# MSP432.net
KiCad netlist of a schematic drawn in Altium Designer
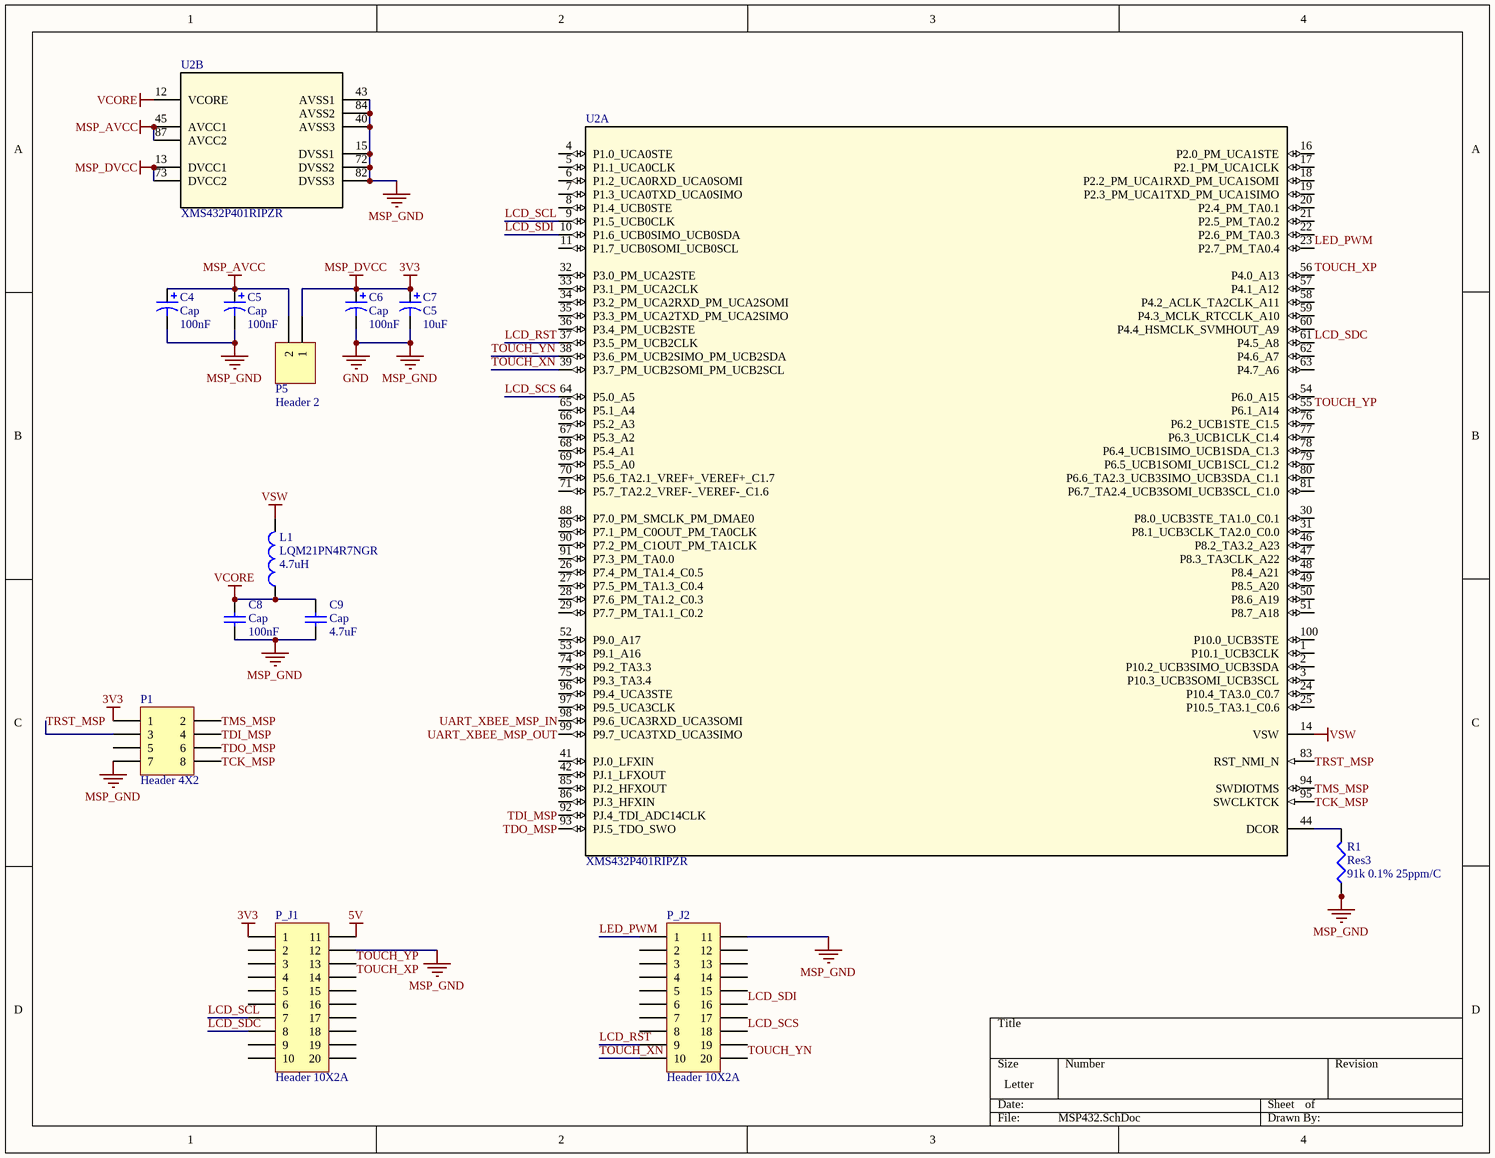
[diagram p0: MSP432.SchDoc]

(export (version "E")
  (design (tool "Eeschema 10.0.6"))
  (components
    (comp (ref "C4")
      (value "Cap")
      (footprint "C0805")
      (description "Polarized Capacitor (Surface Mount)")
      (fields (field (name "ALTIUM_VALUE") "100nF") (field (name "PUBLISHER") "Altium Limited"))
      (libsource (lib "Miscellaneous Devices") (part "Cap Pol3"))
    )
    (comp (ref "C5")
      (value "Cap")
      (footprint "C0805")
      (description "Polarized Capacitor (Surface Mount)")
      (fields (field (name "ALTIUM_VALUE") "100nF") (field (name "PUBLISHER") "Altium Limited"))
      (libsource (lib "Miscellaneous Devices") (part "Cap Pol3"))
    )
    (comp (ref "C6")
      (value "Cap")
      (footprint "C0805")
      (description "Polarized Capacitor (Surface Mount)")
      (fields (field (name "ALTIUM_VALUE") "100nF") (field (name "PUBLISHER") "Altium Limited"))
      (libsource (lib "Miscellaneous Devices") (part "Cap Pol3"))
    )
    (comp (ref "C7")
      (value "C5")
      (footprint "C0805")
      (description "Polarized Capacitor (Surface Mount)")
      (fields (field (name "ALTIUM_VALUE") "10uF") (field (name "PUBLISHER") "Altium Limited"))
      (libsource (lib "Miscellaneous Devices") (part "Cap Pol3"))
    )
    (comp (ref "C8")
      (value "Cap")
      (footprint "C0805")
      (description "Capacitor (Semiconductor SIM Model)")
      (fields (field (name "ALTIUM_VALUE") "100nF") (field (name "PUBLISHER") "Altium Limited"))
      (libsource (lib "Miscellaneous Devices") (part "Cap Semi"))
    )
    (comp (ref "C9")
      (value "Cap")
      (footprint "C0805")
      (description "Capacitor (Semiconductor SIM Model)")
      (fields (field (name "ALTIUM_VALUE") "4.7uF") (field (name "PUBLISHER") "Altium Limited"))
      (libsource (lib "Miscellaneous Devices") (part "Cap Semi"))
    )
    (comp (ref "L1")
      (value "LQM21PN4R7NGR")
      (footprint "6-0805_N")
      (description "Inductor")
      (fields (field (name "ALTIUM_VALUE") "4.7uH") (field (name "PUBLISHER") "Altium Limited"))
      (libsource (lib "Miscellaneous Devices") (part "Inductor"))
    )
    (comp (ref "P1")
      (value "Header 4X2")
      (footprint "HDR2X4")
      (description "Header, 4-Pin, Dual row")
      (fields (field (name "PUBLISHER") "Altium Limited"))
      (libsource (lib "Miscellaneous Connectors") (part "Header 4X2"))
    )
    (comp (ref "P5")
      (value "Header 2")
      (footprint "HDR1X2")
      (description "Header, 2-Pin")
      (fields (field (name "PUBLISHER") "Altium Limited"))
      (libsource (lib "Miscellaneous Connectors") (part "Header 2"))
    )
    (comp (ref "P_J1")
      (value "Header 10X2A")
      (footprint "HDR2X10_CEN")
      (description "Header, 10-Pin, Dual row")
      (fields (field (name "PUBLISHER") "Altium Limited"))
      (libsource (lib "Miscellaneous Connectors") (part "Header 10X2A"))
    )
    (comp (ref "P_J2")
      (value "Header 10X2A")
      (footprint "HDR2X10_CEN")
      (description "Header, 10-Pin, Dual row")
      (fields (field (name "PUBLISHER") "Altium Limited"))
      (libsource (lib "Miscellaneous Connectors") (part "Header 10X2A"))
    )
    (comp (ref "R1")
      (value "Res3")
      (footprint "14-1210")
      (description "Resistor")
      (fields (field (name "ALTIUM_VALUE") "91k 0.1% 25ppm/C") (field (name "PUBLISHER") "Altium Limited"))
      (libsource (lib "Miscellaneous Devices") (part "Res3"))
    )
    (comp (ref "U2")
      (value "XMS432P401RIPZR")
      (footprint "PZ0100A_N")
      (description "Imported")
      (fields (field (name "MANUFACTURER") "Texas Instruments"))
      (libsource (lib "XMS432P401R") (part "XMS432P401RIPZR"))
    )
  )
  (nets
    (net (code "1") (name "/LCD_RST") (class "Default")
      (node (ref "P_J2") (pin "9") (pinfunction "9_9") (pintype "passive"))
      (node (ref "U2") (pin "37") (pinfunction "P3.5_PM_UCB2CLK_37") (pintype "bidirectional"))
    )
    (net (code "2") (name "/LCD_SCL") (class "Default")
      (node (ref "P_J1") (pin "7") (pinfunction "7_7") (pintype "passive"))
      (node (ref "U2") (pin "9") (pinfunction "P1.5_UCB0CLK_9") (pintype "bidirectional"))
    )
    (net (code "3") (name "/LCD_SCS") (class "Default")
      (node (ref "P_J2") (pin "18") (pinfunction "18_18") (pintype "passive"))
      (node (ref "U2") (pin "64") (pinfunction "P5.0_A5_64") (pintype "bidirectional"))
    )
    (net (code "4") (name "/LCD_SDC") (class "Default")
      (node (ref "P_J1") (pin "8") (pinfunction "8_8") (pintype "passive"))
      (node (ref "U2") (pin "61") (pinfunction "P4.5_A8_61") (pintype "bidirectional"))
    )
    (net (code "5") (name "/LCD_SDI") (class "Default")
      (node (ref "P_J2") (pin "16") (pinfunction "16_16") (pintype "passive"))
      (node (ref "U2") (pin "10") (pinfunction "P1.6_UCB0SIMO_UCB0SDA_10") (pintype "bidirectional"))
    )
    (net (code "6") (name "/LED_PWM") (class "Default")
      (node (ref "P_J2") (pin "1") (pinfunction "1_1") (pintype "passive"))
      (node (ref "U2") (pin "23") (pinfunction "P2.7_PM_TA0.4_23") (pintype "bidirectional"))
    )
    (net (code "7") (name "/TCK_MSP") (class "Default")
      (node (ref "P1") (pin "8") (pinfunction "8_8") (pintype "passive"))
      (node (ref "U2") (pin "95") (pinfunction "SWCLKTCK_95") (pintype "input"))
    )
    (net (code "8") (name "/TDI_MSP") (class "Default")
      (node (ref "P1") (pin "4") (pinfunction "4_4") (pintype "passive"))
      (node (ref "U2") (pin "92") (pinfunction "PJ.4_TDI_ADC14CLK_92") (pintype "bidirectional"))
    )
    (net (code "9") (name "/TDO_MSP") (class "Default")
      (node (ref "P1") (pin "6") (pinfunction "6_6") (pintype "passive"))
      (node (ref "U2") (pin "93") (pinfunction "PJ.5_TDO_SWO_93") (pintype "bidirectional"))
    )
    (net (code "10") (name "/TMS_MSP") (class "Default")
      (node (ref "P1") (pin "2") (pinfunction "2_2") (pintype "passive"))
      (node (ref "U2") (pin "94") (pinfunction "SWDIOTMS_94") (pintype "bidirectional"))
    )
    (net (code "11") (name "/TOUCH_XN") (class "Default")
      (node (ref "P_J2") (pin "10") (pinfunction "10_10") (pintype "passive"))
      (node (ref "U2") (pin "39") (pinfunction "P3.7_PM_UCB2SOMI_PM_UCB2SCL_39") (pintype "bidirectional"))
    )
    (net (code "12") (name "/TOUCH_XP") (class "Default")
      (node (ref "P_J1") (pin "14") (pinfunction "14_14") (pintype "passive"))
      (node (ref "U2") (pin "56") (pinfunction "P4.0_A13_56") (pintype "bidirectional"))
    )
    (net (code "13") (name "/TOUCH_YN") (class "Default")
      (node (ref "P_J2") (pin "20") (pinfunction "20_20") (pintype "passive"))
      (node (ref "U2") (pin "38") (pinfunction "P3.6_PM_UCB2SIMO_PM_UCB2SDA_38") (pintype "bidirectional"))
    )
    (net (code "14") (name "/TOUCH_YP") (class "Default")
      (node (ref "P_J1") (pin "13") (pinfunction "13_13") (pintype "passive"))
      (node (ref "U2") (pin "55") (pinfunction "P6.1_A14_55") (pintype "bidirectional"))
    )
    (net (code "15") (name "/TRST_MSP") (class "Default")
      (node (ref "P1") (pin "3") (pinfunction "3_3") (pintype "passive"))
      (node (ref "U2") (pin "83") (pinfunction "RST_NMI_N_83") (pintype "input"))
    )
    (net (code "16") (name "/UART_XBEE_MSP_IN") (class "Default")
      (node (ref "U2") (pin "98") (pinfunction "P9.6_UCA3RXD_UCA3SOMI_98") (pintype "bidirectional"))
    )
    (net (code "17") (name "/UART_XBEE_MSP_OUT") (class "Default")
      (node (ref "U2") (pin "99") (pinfunction "P9.7_UCA3TXD_UCA3SIMO_99") (pintype "bidirectional"))
    )
    (net (code "18") (name "3V3") (class "Default")
      (node (ref "C6") (pin "1") (pinfunction "1_1") (pintype "passive"))
      (node (ref "C7") (pin "1") (pinfunction "1_1") (pintype "passive"))
      (node (ref "P1") (pin "1") (pinfunction "1_1") (pintype "passive"))
      (node (ref "P5") (pin "1") (pinfunction "1_1") (pintype "passive"))
      (node (ref "P_J1") (pin "1") (pinfunction "1_1") (pintype "passive"))
      (node (ref "U2") (pin "13") (pinfunction "DVCC1_13") (pintype "power_in"))
      (node (ref "U2") (pin "73") (pinfunction "DVCC2_73") (pintype "power_in"))
    )
    (net (code "19") (name "5V") (class "Default")
      (node (ref "P_J1") (pin "11") (pinfunction "11_11") (pintype "passive"))
    )
    (net (code "20") (name "GND") (class "Default")
      (node (ref "C4") (pin "2") (pinfunction "2_2") (pintype "passive"))
      (node (ref "C5") (pin "2") (pinfunction "2_2") (pintype "passive"))
      (node (ref "C6") (pin "2") (pinfunction "2_2") (pintype "passive"))
      (node (ref "C7") (pin "2") (pinfunction "2_2") (pintype "passive"))
      (node (ref "C8") (pin "1") (pinfunction "1_1") (pintype "passive"))
      (node (ref "C9") (pin "2") (pinfunction "2_2") (pintype "passive"))
      (node (ref "P1") (pin "7") (pinfunction "7_7") (pintype "passive"))
      (node (ref "P_J1") (pin "12") (pinfunction "12_12") (pintype "passive"))
      (node (ref "P_J2") (pin "11") (pinfunction "11_11") (pintype "passive"))
      (node (ref "R1") (pin "1") (pinfunction "1_1") (pintype "passive"))
      (node (ref "U2") (pin "15") (pinfunction "DVSS1_15") (pintype "power_in"))
      (node (ref "U2") (pin "40") (pinfunction "AVSS3_40") (pintype "power_in"))
      (node (ref "U2") (pin "43") (pinfunction "AVSS1_43") (pintype "power_in"))
      (node (ref "U2") (pin "72") (pinfunction "DVSS2_72") (pintype "power_in"))
      (node (ref "U2") (pin "82") (pinfunction "DVSS3_82") (pintype "power_in"))
      (node (ref "U2") (pin "84") (pinfunction "AVSS2_84") (pintype "power_in"))
    )
    (net (code "21") (name "MSP_AVCC") (class "Default")
      (node (ref "C4") (pin "1") (pinfunction "1_1") (pintype "passive"))
      (node (ref "C5") (pin "1") (pinfunction "1_1") (pintype "passive"))
      (node (ref "P5") (pin "2") (pinfunction "2_2") (pintype "passive"))
      (node (ref "U2") (pin "45") (pinfunction "AVCC1_45") (pintype "power_in"))
      (node (ref "U2") (pin "87") (pinfunction "AVCC2_87") (pintype "power_in"))
    )
    (net (code "22") (name "Net-(U2A-DCOR)") (class "Default")
      (node (ref "R1") (pin "2") (pinfunction "2_2") (pintype "passive"))
      (node (ref "U2") (pin "44") (pinfunction "DCOR_44") (pintype "passive"))
    )
    (net (code "23") (name "VCORE") (class "Default")
      (node (ref "C8") (pin "2") (pinfunction "2_2") (pintype "passive"))
      (node (ref "C9") (pin "1") (pinfunction "1_1") (pintype "passive"))
      (node (ref "L1") (pin "1") (pinfunction "1_1") (pintype "passive"))
      (node (ref "U2") (pin "12") (pinfunction "VCORE_12") (pintype "power_in"))
    )
    (net (code "24") (name "VSW") (class "Default")
      (node (ref "L1") (pin "2") (pinfunction "2_2") (pintype "passive"))
      (node (ref "U2") (pin "14") (pinfunction "VSW_14") (pintype "passive"))
    )
    (net (code "25") (name "unconnected-(P1-Pad5)") (class "Default")
      (node (ref "P1") (pin "5") (pinfunction "5_5") (pintype "passive"))
    )
    (net (code "26") (name "unconnected-(P_J1-Pad2)") (class "Default")
      (node (ref "P_J1") (pin "2") (pinfunction "2_2") (pintype "passive"))
    )
    (net (code "27") (name "unconnected-(P_J1-Pad3)") (class "Default")
      (node (ref "P_J1") (pin "3") (pinfunction "3_3") (pintype "passive"))
    )
    (net (code "28") (name "unconnected-(P_J1-Pad4)") (class "Default")
      (node (ref "P_J1") (pin "4") (pinfunction "4_4") (pintype "passive"))
    )
    (net (code "29") (name "unconnected-(P_J1-Pad5)") (class "Default")
      (node (ref "P_J1") (pin "5") (pinfunction "5_5") (pintype "passive"))
    )
    (net (code "30") (name "unconnected-(P_J1-Pad6)") (class "Default")
      (node (ref "P_J1") (pin "6") (pinfunction "6_6") (pintype "passive"))
    )
    (net (code "31") (name "unconnected-(P_J1-Pad9)") (class "Default")
      (node (ref "P_J1") (pin "9") (pinfunction "9_9") (pintype "passive"))
    )
    (net (code "32") (name "unconnected-(P_J1-Pad10)") (class "Default")
      (node (ref "P_J1") (pin "10") (pinfunction "10_10") (pintype "passive"))
    )
    (net (code "33") (name "unconnected-(P_J1-Pad15)") (class "Default")
      (node (ref "P_J1") (pin "15") (pinfunction "15_15") (pintype "passive"))
    )
    (net (code "34") (name "unconnected-(P_J1-Pad16)") (class "Default")
      (node (ref "P_J1") (pin "16") (pinfunction "16_16") (pintype "passive"))
    )
    (net (code "35") (name "unconnected-(P_J1-Pad17)") (class "Default")
      (node (ref "P_J1") (pin "17") (pinfunction "17_17") (pintype "passive"))
    )
    (net (code "36") (name "unconnected-(P_J1-Pad18)") (class "Default")
      (node (ref "P_J1") (pin "18") (pinfunction "18_18") (pintype "passive"))
    )
    (net (code "37") (name "unconnected-(P_J1-Pad19)") (class "Default")
      (node (ref "P_J1") (pin "19") (pinfunction "19_19") (pintype "passive"))
    )
    (net (code "38") (name "unconnected-(P_J1-Pad20)") (class "Default")
      (node (ref "P_J1") (pin "20") (pinfunction "20_20") (pintype "passive"))
    )
    (net (code "39") (name "unconnected-(P_J2-Pad2)") (class "Default")
      (node (ref "P_J2") (pin "2") (pinfunction "2_2") (pintype "passive"))
    )
    (net (code "40") (name "unconnected-(P_J2-Pad3)") (class "Default")
      (node (ref "P_J2") (pin "3") (pinfunction "3_3") (pintype "passive"))
    )
    (net (code "41") (name "unconnected-(P_J2-Pad4)") (class "Default")
      (node (ref "P_J2") (pin "4") (pinfunction "4_4") (pintype "passive"))
    )
    (net (code "42") (name "unconnected-(P_J2-Pad5)") (class "Default")
      (node (ref "P_J2") (pin "5") (pinfunction "5_5") (pintype "passive"))
    )
    (net (code "43") (name "unconnected-(P_J2-Pad6)") (class "Default")
      (node (ref "P_J2") (pin "6") (pinfunction "6_6") (pintype "passive"))
    )
    (net (code "44") (name "unconnected-(P_J2-Pad7)") (class "Default")
      (node (ref "P_J2") (pin "7") (pinfunction "7_7") (pintype "passive"))
    )
    (net (code "45") (name "unconnected-(P_J2-Pad8)") (class "Default")
      (node (ref "P_J2") (pin "8") (pinfunction "8_8") (pintype "passive"))
    )
    (net (code "46") (name "unconnected-(P_J2-Pad12)") (class "Default")
      (node (ref "P_J2") (pin "12") (pinfunction "12_12") (pintype "passive"))
    )
    (net (code "47") (name "unconnected-(P_J2-Pad13)") (class "Default")
      (node (ref "P_J2") (pin "13") (pinfunction "13_13") (pintype "passive"))
    )
    (net (code "48") (name "unconnected-(P_J2-Pad14)") (class "Default")
      (node (ref "P_J2") (pin "14") (pinfunction "14_14") (pintype "passive"))
    )
    (net (code "49") (name "unconnected-(P_J2-Pad15)") (class "Default")
      (node (ref "P_J2") (pin "15") (pinfunction "15_15") (pintype "passive"))
    )
    (net (code "50") (name "unconnected-(P_J2-Pad17)") (class "Default")
      (node (ref "P_J2") (pin "17") (pinfunction "17_17") (pintype "passive"))
    )
    (net (code "51") (name "unconnected-(P_J2-Pad19)") (class "Default")
      (node (ref "P_J2") (pin "19") (pinfunction "19_19") (pintype "passive"))
    )
    (net (code "52") (name "unconnected-(U2A-P1.0_UCA0STE-Pad4)") (class "Default")
      (node (ref "U2") (pin "4") (pinfunction "P1.0_UCA0STE_4") (pintype "bidirectional"))
    )
    (net (code "53") (name "unconnected-(U2A-P1.1_UCA0CLK-Pad5)") (class "Default")
      (node (ref "U2") (pin "5") (pinfunction "P1.1_UCA0CLK_5") (pintype "bidirectional"))
    )
    (net (code "54") (name "unconnected-(U2A-P1.2_UCA0RXD_UCA0SOMI-Pad6)") (class "Default")
      (node (ref "U2") (pin "6") (pinfunction "P1.2_UCA0RXD_UCA0SOMI_6") (pintype "bidirectional"))
    )
    (net (code "55") (name "unconnected-(U2A-P1.3_UCA0TXD_UCA0SIMO-Pad7)") (class "Default")
      (node (ref "U2") (pin "7") (pinfunction "P1.3_UCA0TXD_UCA0SIMO_7") (pintype "bidirectional"))
    )
    (net (code "56") (name "unconnected-(U2A-P1.4_UCB0STE-Pad8)") (class "Default")
      (node (ref "U2") (pin "8") (pinfunction "P1.4_UCB0STE_8") (pintype "bidirectional"))
    )
    (net (code "57") (name "unconnected-(U2A-P1.7_UCB0SOMI_UCB0SCL-Pad11)") (class "Default")
      (node (ref "U2") (pin "11") (pinfunction "P1.7_UCB0SOMI_UCB0SCL_11") (pintype "bidirectional"))
    )
    (net (code "58") (name "unconnected-(U2A-P2.0_PM_UCA1STE-Pad16)") (class "Default")
      (node (ref "U2") (pin "16") (pinfunction "P2.0_PM_UCA1STE_16") (pintype "bidirectional"))
    )
    (net (code "59") (name "unconnected-(U2A-P2.1_PM_UCA1CLK-Pad17)") (class "Default")
      (node (ref "U2") (pin "17") (pinfunction "P2.1_PM_UCA1CLK_17") (pintype "bidirectional"))
    )
    (net (code "60") (name "unconnected-(U2A-P2.2_PM_UCA1RXD_PM_UCA1SOMI-Pad18)") (class "Default")
      (node (ref "U2") (pin "18") (pinfunction "P2.2_PM_UCA1RXD_PM_UCA1SOMI_18") (pintype "bidirectional"))
    )
    (net (code "61") (name "unconnected-(U2A-P2.3_PM_UCA1TXD_PM_UCA1SIMO-Pad19)") (class "Default")
      (node (ref "U2") (pin "19") (pinfunction "P2.3_PM_UCA1TXD_PM_UCA1SIMO_19") (pintype "bidirectional"))
    )
    (net (code "62") (name "unconnected-(U2A-P2.4_PM_TA0.1-Pad20)") (class "Default")
      (node (ref "U2") (pin "20") (pinfunction "P2.4_PM_TA0.1_20") (pintype "bidirectional"))
    )
    (net (code "63") (name "unconnected-(U2A-P2.5_PM_TA0.2-Pad21)") (class "Default")
      (node (ref "U2") (pin "21") (pinfunction "P2.5_PM_TA0.2_21") (pintype "bidirectional"))
    )
    (net (code "64") (name "unconnected-(U2A-P2.6_PM_TA0.3-Pad22)") (class "Default")
      (node (ref "U2") (pin "22") (pinfunction "P2.6_PM_TA0.3_22") (pintype "bidirectional"))
    )
    (net (code "65") (name "unconnected-(U2A-P3.0_PM_UCA2STE-Pad32)") (class "Default")
      (node (ref "U2") (pin "32") (pinfunction "P3.0_PM_UCA2STE_32") (pintype "bidirectional"))
    )
    (net (code "66") (name "unconnected-(U2A-P3.1_PM_UCA2CLK-Pad33)") (class "Default")
      (node (ref "U2") (pin "33") (pinfunction "P3.1_PM_UCA2CLK_33") (pintype "bidirectional"))
    )
    (net (code "67") (name "unconnected-(U2A-P3.2_PM_UCA2RXD_PM_UCA2SOMI-Pad34)") (class "Default")
      (node (ref "U2") (pin "34") (pinfunction "P3.2_PM_UCA2RXD_PM_UCA2SOMI_34") (pintype "bidirectional"))
    )
    (net (code "68") (name "unconnected-(U2A-P3.3_PM_UCA2TXD_PM_UCA2SIMO-Pad35)") (class "Default")
      (node (ref "U2") (pin "35") (pinfunction "P3.3_PM_UCA2TXD_PM_UCA2SIMO_35") (pintype "bidirectional"))
    )
    (net (code "69") (name "unconnected-(U2A-P3.4_PM_UCB2STE-Pad36)") (class "Default")
      (node (ref "U2") (pin "36") (pinfunction "P3.4_PM_UCB2STE_36") (pintype "bidirectional"))
    )
    (net (code "70") (name "unconnected-(U2A-P4.1_A12-Pad57)") (class "Default")
      (node (ref "U2") (pin "57") (pinfunction "P4.1_A12_57") (pintype "bidirectional"))
    )
    (net (code "71") (name "unconnected-(U2A-P4.2_ACLK_TA2CLK_A11-Pad58)") (class "Default")
      (node (ref "U2") (pin "58") (pinfunction "P4.2_ACLK_TA2CLK_A11_58") (pintype "bidirectional"))
    )
    (net (code "72") (name "unconnected-(U2A-P4.3_MCLK_RTCCLK_A10-Pad59)") (class "Default")
      (node (ref "U2") (pin "59") (pinfunction "P4.3_MCLK_RTCCLK_A10_59") (pintype "bidirectional"))
    )
    (net (code "73") (name "unconnected-(U2A-P4.4_HSMCLK_SVMHOUT_A9-Pad60)") (class "Default")
      (node (ref "U2") (pin "60") (pinfunction "P4.4_HSMCLK_SVMHOUT_A9_60") (pintype "bidirectional"))
    )
    (net (code "74") (name "unconnected-(U2A-P4.6_A7-Pad62)") (class "Default")
      (node (ref "U2") (pin "62") (pinfunction "P4.6_A7_62") (pintype "bidirectional"))
    )
    (net (code "75") (name "unconnected-(U2A-P4.7_A6-Pad63)") (class "Default")
      (node (ref "U2") (pin "63") (pinfunction "P4.7_A6_63") (pintype "bidirectional"))
    )
    (net (code "76") (name "unconnected-(U2A-P5.1_A4-Pad65)") (class "Default")
      (node (ref "U2") (pin "65") (pinfunction "P5.1_A4_65") (pintype "bidirectional"))
    )
    (net (code "77") (name "unconnected-(U2A-P5.2_A3-Pad66)") (class "Default")
      (node (ref "U2") (pin "66") (pinfunction "P5.2_A3_66") (pintype "bidirectional"))
    )
    (net (code "78") (name "unconnected-(U2A-P5.3_A2-Pad67)") (class "Default")
      (node (ref "U2") (pin "67") (pinfunction "P5.3_A2_67") (pintype "bidirectional"))
    )
    (net (code "79") (name "unconnected-(U2A-P5.4_A1-Pad68)") (class "Default")
      (node (ref "U2") (pin "68") (pinfunction "P5.4_A1_68") (pintype "bidirectional"))
    )
    (net (code "80") (name "unconnected-(U2A-P5.5_A0-Pad69)") (class "Default")
      (node (ref "U2") (pin "69") (pinfunction "P5.5_A0_69") (pintype "bidirectional"))
    )
    (net (code "81") (name "unconnected-(U2A-P5.6_TA2.1_VREF+_VEREF+_C1.7-Pad70)") (class "Default")
      (node (ref "U2") (pin "70") (pinfunction "P5.6_TA2.1_VREF+_VEREF+_C1.7_70") (pintype "bidirectional"))
    )
    (net (code "82") (name "unconnected-(U2A-P5.7_TA2.2_VREF-_VEREF-_C1.6-Pad71)") (class "Default")
      (node (ref "U2") (pin "71") (pinfunction "P5.7_TA2.2_VREF-_VEREF-_C1.6_71") (pintype "bidirectional"))
    )
    (net (code "83") (name "unconnected-(U2A-P6.0_A15-Pad54)") (class "Default")
      (node (ref "U2") (pin "54") (pinfunction "P6.0_A15_54") (pintype "bidirectional"))
    )
    (net (code "84") (name "unconnected-(U2A-P6.2_UCB1STE_C1.5-Pad76)") (class "Default")
      (node (ref "U2") (pin "76") (pinfunction "P6.2_UCB1STE_C1.5_76") (pintype "bidirectional"))
    )
    (net (code "85") (name "unconnected-(U2A-P6.3_UCB1CLK_C1.4-Pad77)") (class "Default")
      (node (ref "U2") (pin "77") (pinfunction "P6.3_UCB1CLK_C1.4_77") (pintype "bidirectional"))
    )
    (net (code "86") (name "unconnected-(U2A-P6.4_UCB1SIMO_UCB1SDA_C1.3-Pad78)") (class "Default")
      (node (ref "U2") (pin "78") (pinfunction "P6.4_UCB1SIMO_UCB1SDA_C1.3_78") (pintype "bidirectional"))
    )
    (net (code "87") (name "unconnected-(U2A-P6.5_UCB1SOMI_UCB1SCL_C1.2-Pad79)") (class "Default")
      (node (ref "U2") (pin "79") (pinfunction "P6.5_UCB1SOMI_UCB1SCL_C1.2_79") (pintype "bidirectional"))
    )
    (net (code "88") (name "unconnected-(U2A-P6.6_TA2.3_UCB3SIMO_UCB3SDA_C1.1-Pad80)") (class "Default")
      (node (ref "U2") (pin "80") (pinfunction "P6.6_TA2.3_UCB3SIMO_UCB3SDA_C1.1_80") (pintype "bidirectional"))
    )
    (net (code "89") (name "unconnected-(U2A-P6.7_TA2.4_UCB3SOMI_UCB3SCL_C1.0-Pad81)") (class "Default")
      (node (ref "U2") (pin "81") (pinfunction "P6.7_TA2.4_UCB3SOMI_UCB3SCL_C1.0_81") (pintype "bidirectional"))
    )
    (net (code "90") (name "unconnected-(U2A-P7.0_PM_SMCLK_PM_DMAE0-Pad88)") (class "Default")
      (node (ref "U2") (pin "88") (pinfunction "P7.0_PM_SMCLK_PM_DMAE0_88") (pintype "bidirectional"))
    )
    (net (code "91") (name "unconnected-(U2A-P7.1_PM_C0OUT_PM_TA0CLK-Pad89)") (class "Default")
      (node (ref "U2") (pin "89") (pinfunction "P7.1_PM_C0OUT_PM_TA0CLK_89") (pintype "bidirectional"))
    )
    (net (code "92") (name "unconnected-(U2A-P7.2_PM_C1OUT_PM_TA1CLK-Pad90)") (class "Default")
      (node (ref "U2") (pin "90") (pinfunction "P7.2_PM_C1OUT_PM_TA1CLK_90") (pintype "bidirectional"))
    )
    (net (code "93") (name "unconnected-(U2A-P7.3_PM_TA0.0-Pad91)") (class "Default")
      (node (ref "U2") (pin "91") (pinfunction "P7.3_PM_TA0.0_91") (pintype "bidirectional"))
    )
    (net (code "94") (name "unconnected-(U2A-P7.4_PM_TA1.4_C0.5-Pad26)") (class "Default")
      (node (ref "U2") (pin "26") (pinfunction "P7.4_PM_TA1.4_C0.5_26") (pintype "bidirectional"))
    )
    (net (code "95") (name "unconnected-(U2A-P7.5_PM_TA1.3_C0.4-Pad27)") (class "Default")
      (node (ref "U2") (pin "27") (pinfunction "P7.5_PM_TA1.3_C0.4_27") (pintype "bidirectional"))
    )
    (net (code "96") (name "unconnected-(U2A-P7.6_PM_TA1.2_C0.3-Pad28)") (class "Default")
      (node (ref "U2") (pin "28") (pinfunction "P7.6_PM_TA1.2_C0.3_28") (pintype "bidirectional"))
    )
    (net (code "97") (name "unconnected-(U2A-P7.7_PM_TA1.1_C0.2-Pad29)") (class "Default")
      (node (ref "U2") (pin "29") (pinfunction "P7.7_PM_TA1.1_C0.2_29") (pintype "bidirectional"))
    )
    (net (code "98") (name "unconnected-(U2A-P8.0_UCB3STE_TA1.0_C0.1-Pad30)") (class "Default")
      (node (ref "U2") (pin "30") (pinfunction "P8.0_UCB3STE_TA1.0_C0.1_30") (pintype "bidirectional"))
    )
    (net (code "99") (name "unconnected-(U2A-P8.1_UCB3CLK_TA2.0_C0.0-Pad31)") (class "Default")
      (node (ref "U2") (pin "31") (pinfunction "P8.1_UCB3CLK_TA2.0_C0.0_31") (pintype "bidirectional"))
    )
    (net (code "100") (name "unconnected-(U2A-P8.2_TA3.2_A23-Pad46)") (class "Default")
      (node (ref "U2") (pin "46") (pinfunction "P8.2_TA3.2_A23_46") (pintype "bidirectional"))
    )
    (net (code "101") (name "unconnected-(U2A-P8.3_TA3CLK_A22-Pad47)") (class "Default")
      (node (ref "U2") (pin "47") (pinfunction "P8.3_TA3CLK_A22_47") (pintype "bidirectional"))
    )
    (net (code "102") (name "unconnected-(U2A-P8.4_A21-Pad48)") (class "Default")
      (node (ref "U2") (pin "48") (pinfunction "P8.4_A21_48") (pintype "bidirectional"))
    )
    (net (code "103") (name "unconnected-(U2A-P8.5_A20-Pad49)") (class "Default")
      (node (ref "U2") (pin "49") (pinfunction "P8.5_A20_49") (pintype "bidirectional"))
    )
    (net (code "104") (name "unconnected-(U2A-P8.6_A19-Pad50)") (class "Default")
      (node (ref "U2") (pin "50") (pinfunction "P8.6_A19_50") (pintype "bidirectional"))
    )
    (net (code "105") (name "unconnected-(U2A-P8.7_A18-Pad51)") (class "Default")
      (node (ref "U2") (pin "51") (pinfunction "P8.7_A18_51") (pintype "bidirectional"))
    )
    (net (code "106") (name "unconnected-(U2A-P9.0_A17-Pad52)") (class "Default")
      (node (ref "U2") (pin "52") (pinfunction "P9.0_A17_52") (pintype "bidirectional"))
    )
    (net (code "107") (name "unconnected-(U2A-P9.1_A16-Pad53)") (class "Default")
      (node (ref "U2") (pin "53") (pinfunction "P9.1_A16_53") (pintype "bidirectional"))
    )
    (net (code "108") (name "unconnected-(U2A-P9.2_TA3.3-Pad74)") (class "Default")
      (node (ref "U2") (pin "74") (pinfunction "P9.2_TA3.3_74") (pintype "bidirectional"))
    )
    (net (code "109") (name "unconnected-(U2A-P9.3_TA3.4-Pad75)") (class "Default")
      (node (ref "U2") (pin "75") (pinfunction "P9.3_TA3.4_75") (pintype "bidirectional"))
    )
    (net (code "110") (name "unconnected-(U2A-P9.4_UCA3STE-Pad96)") (class "Default")
      (node (ref "U2") (pin "96") (pinfunction "P9.4_UCA3STE_96") (pintype "bidirectional"))
    )
    (net (code "111") (name "unconnected-(U2A-P9.5_UCA3CLK-Pad97)") (class "Default")
      (node (ref "U2") (pin "97") (pinfunction "P9.5_UCA3CLK_97") (pintype "bidirectional"))
    )
    (net (code "112") (name "unconnected-(U2A-P10.0_UCB3STE-Pad100)") (class "Default")
      (node (ref "U2") (pin "100") (pinfunction "P10.0_UCB3STE_100") (pintype "bidirectional"))
    )
    (net (code "113") (name "unconnected-(U2A-P10.1_UCB3CLK-Pad1)") (class "Default")
      (node (ref "U2") (pin "1") (pinfunction "P10.1_UCB3CLK_1") (pintype "bidirectional"))
    )
    (net (code "114") (name "unconnected-(U2A-P10.2_UCB3SIMO_UCB3SDA-Pad2)") (class "Default")
      (node (ref "U2") (pin "2") (pinfunction "P10.2_UCB3SIMO_UCB3SDA_2") (pintype "bidirectional"))
    )
    (net (code "115") (name "unconnected-(U2A-P10.3_UCB3SOMI_UCB3SCL-Pad3)") (class "Default")
      (node (ref "U2") (pin "3") (pinfunction "P10.3_UCB3SOMI_UCB3SCL_3") (pintype "bidirectional"))
    )
    (net (code "116") (name "unconnected-(U2A-P10.4_TA3.0_C0.7-Pad24)") (class "Default")
      (node (ref "U2") (pin "24") (pinfunction "P10.4_TA3.0_C0.7_24") (pintype "bidirectional"))
    )
    (net (code "117") (name "unconnected-(U2A-P10.5_TA3.1_C0.6-Pad25)") (class "Default")
      (node (ref "U2") (pin "25") (pinfunction "P10.5_TA3.1_C0.6_25") (pintype "bidirectional"))
    )
    (net (code "118") (name "unconnected-(U2A-PJ.0_LFXIN-Pad41)") (class "Default")
      (node (ref "U2") (pin "41") (pinfunction "PJ.0_LFXIN_41") (pintype "bidirectional"))
    )
    (net (code "119") (name "unconnected-(U2A-PJ.1_LFXOUT-Pad42)") (class "Default")
      (node (ref "U2") (pin "42") (pinfunction "PJ.1_LFXOUT_42") (pintype "bidirectional"))
    )
    (net (code "120") (name "unconnected-(U2A-PJ.2_HFXOUT-Pad85)") (class "Default")
      (node (ref "U2") (pin "85") (pinfunction "PJ.2_HFXOUT_85") (pintype "bidirectional"))
    )
    (net (code "121") (name "unconnected-(U2A-PJ.3_HFXIN-Pad86)") (class "Default")
      (node (ref "U2") (pin "86") (pinfunction "PJ.3_HFXIN_86") (pintype "bidirectional"))
    )
  )
)
